# Sheet2.net
KiCad netlist of a schematic drawn in Altium Designer
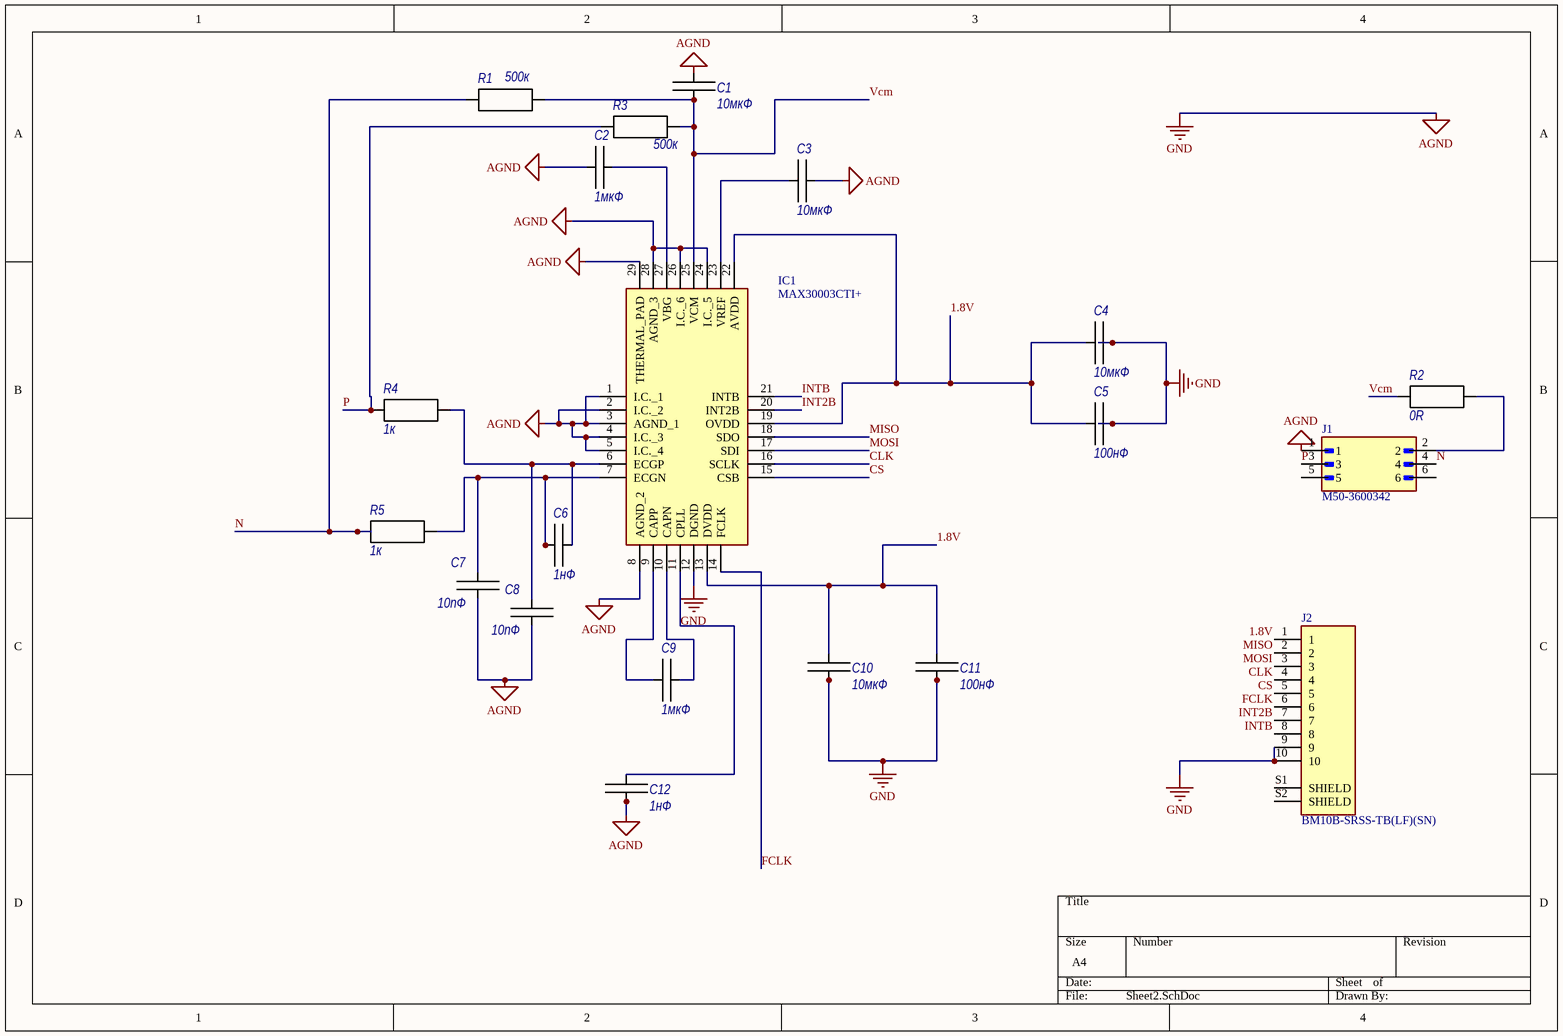
[diagram p0: Sheet2.SchDoc]

(export (version "E")
  (design (tool "Eeschema 10.0.6"))
  (components
    (comp (ref "C1")
      (value "10мкФ")
      (footprint "C0402C")
      (description "CC0402JRX7R9BB103, 0402 X5R 0,01 uF 50V")
      (fields (field (name "PART NUMBER") "CC0402JRX7R9BB103") (field (name "MANUFACTURER") "Yageo"))
      (libsource (lib "lib") (part "Cap"))
    )
    (comp (ref "C2")
      (value "1мкФ")
      (footprint "C0402C")
      (description "CC0402JRX7R9BB103, 0402 X5R 0,01 uF 50V")
      (fields (field (name "PART NUMBER") "CC0402JRX7R9BB103") (field (name "MANUFACTURER") "Yageo"))
      (libsource (lib "lib") (part "Cap"))
    )
    (comp (ref "C3")
      (value "10мкФ")
      (footprint "C0402C")
      (description "CC0402JRX7R9BB103, 0402 X5R 0,01 uF 50V")
      (fields (field (name "PART NUMBER") "CC0402JRX7R9BB103") (field (name "MANUFACTURER") "Yageo"))
      (libsource (lib "lib") (part "Cap"))
    )
    (comp (ref "C4")
      (value "10мкФ")
      (footprint "C0402C")
      (description "CC0402JRX7R9BB103, 0402 X5R 0,01 uF 50V")
      (fields (field (name "PART NUMBER") "CC0402JRX7R9BB103") (field (name "MANUFACTURER") "Yageo"))
      (libsource (lib "lib") (part "Cap"))
    )
    (comp (ref "C5")
      (value "100нФ")
      (footprint "C0402C")
      (description "CC0402JRX7R9BB103, 0402 X5R 0,01 uF 50V")
      (fields (field (name "PART NUMBER") "CC0402JRX7R9BB103") (field (name "MANUFACTURER") "Yageo"))
      (libsource (lib "lib") (part "Cap"))
    )
    (comp (ref "C6")
      (value "1нФ")
      (footprint "C0402C")
      (description "CC0402JRX7R9BB103, 0402 X5R 0,01 uF 50V")
      (fields (field (name "PART NUMBER") "CC0402JRX7R9BB103") (field (name "MANUFACTURER") "Yageo"))
      (libsource (lib "lib") (part "Cap"))
    )
    (comp (ref "C7")
      (value "10пФ")
      (footprint "C0402C")
      (description "CC0402JRX7R9BB103, 0402 X5R 0,01 uF 50V")
      (fields (field (name "PART NUMBER") "CC0402JRX7R9BB103") (field (name "MANUFACTURER") "Yageo"))
      (libsource (lib "lib") (part "Cap"))
    )
    (comp (ref "C8")
      (value "10пФ")
      (footprint "C0402C")
      (description "CC0402JRX7R9BB103, 0402 X5R 0,01 uF 50V")
      (fields (field (name "PART NUMBER") "CC0402JRX7R9BB103") (field (name "MANUFACTURER") "Yageo"))
      (libsource (lib "lib") (part "Cap"))
    )
    (comp (ref "C9")
      (value "1мкФ")
      (footprint "C0402C")
      (description "CC0402JRX7R9BB103, 0402 X5R 0,01 uF 50V")
      (fields (field (name "PART NUMBER") "CC0402JRX7R9BB103") (field (name "MANUFACTURER") "Yageo"))
      (libsource (lib "lib") (part "Cap"))
    )
    (comp (ref "C10")
      (value "10мкФ")
      (footprint "C0402C")
      (description "CC0402JRX7R9BB103, 0402 X5R 0,01 uF 50V")
      (fields (field (name "PART NUMBER") "CC0402JRX7R9BB103") (field (name "MANUFACTURER") "Yageo"))
      (libsource (lib "lib") (part "Cap"))
    )
    (comp (ref "C11")
      (value "100нФ")
      (footprint "C0402C")
      (description "CC0402JRX7R9BB103, 0402 X5R 0,01 uF 50V")
      (fields (field (name "PART NUMBER") "CC0402JRX7R9BB103") (field (name "MANUFACTURER") "Yageo"))
      (libsource (lib "lib") (part "Cap"))
    )
    (comp (ref "C12")
      (value "1нФ")
      (footprint "C0402C")
      (description "CC0402JRX7R9BB103, 0402 X5R 0,01 uF 50V")
      (fields (field (name "PART NUMBER") "CC0402JRX7R9BB103") (field (name "MANUFACTURER") "Yageo"))
      (libsource (lib "lib") (part "Cap"))
    )
    (comp (ref "IC1")
      (value "MAX30003CTI+")
      (footprint "QFN50P500X500X80-29N")
      (description "Integrated Circuit")
      (fields (field (name "MOUSER PART NUMBER") "700-MAX30003CTI+"))
      (libsource (lib "*") (part "MAX30003CTI+"))
    )
    (comp (ref "J1")
      (value "M50-3600342")
      (footprint "HARWIN_M50-3600342")
      (libsource (lib "M50-3600342") (part "M50-3600342"))
    )
    (comp (ref "J2")
      (value "BM10B-SRSS-TB(LF)(SN)")
      (footprint "JST_BM10B-SRSS-TB(LF)(SN)")
      (description "Connector Header Surface Mount 10 position 0.039 (1.00mm)")
      (fields (field (name "MF") "JST Sales"))
      (libsource (lib "BM10B-SRSS-TB_LF__SN_") (part "BM10B-SRSS-TB(LF)(SN)"))
    )
    (comp (ref "R1")
      (value "500к")
      (footprint "C0402R")
      (description "Р1-12М-0402-0,  SMD 0402")
      (fields (field (name "PART NUMBER") "Р1-12М-0402-0") (field (name "MANUFACTURER") "НПО ЭРКОН"))
      (libsource (lib "lib") (part "res"))
    )
    (comp (ref "R2")
      (value "0R")
      (footprint "C0402R")
      (description "Р1-12М-0402-0,  SMD 0402")
      (fields (field (name "PART NUMBER") "Р1-12М-0402-0") (field (name "MANUFACTURER") "НПО ЭРКОН"))
      (libsource (lib "lib") (part "res"))
    )
    (comp (ref "R3")
      (value "500к")
      (footprint "C0402R")
      (description "Р1-12М-0402-0,  SMD 0402")
      (fields (field (name "PART NUMBER") "Р1-12М-0402-0") (field (name "MANUFACTURER") "НПО ЭРКОН"))
      (libsource (lib "lib") (part "res"))
    )
    (comp (ref "R4")
      (value "1к")
      (footprint "C0402R")
      (description "Р1-12М-0402-0,  SMD 0402")
      (fields (field (name "PART NUMBER") "Р1-12М-0402-0") (field (name "MANUFACTURER") "НПО ЭРКОН"))
      (libsource (lib "lib") (part "res"))
    )
    (comp (ref "R5")
      (value "1к")
      (footprint "C0402R")
      (description "Р1-12М-0402-0,  SMD 0402")
      (fields (field (name "PART NUMBER") "Р1-12М-0402-0") (field (name "MANUFACTURER") "НПО ЭРКОН"))
      (libsource (lib "lib") (part "res"))
    )
  )
  (nets
    (net (code "1") (name "/1.8V") (class "Default")
      (node (ref "C10") (pin "1") (pinfunction "1_1") (pintype "passive"))
      (node (ref "C11") (pin "1") (pinfunction "1_1") (pintype "passive"))
      (node (ref "C4") (pin "1") (pinfunction "1_1") (pintype "passive"))
      (node (ref "C5") (pin "1") (pinfunction "1_1") (pintype "passive"))
      (node (ref "IC1") (pin "13") (pinfunction "DVDD_13") (pintype "passive"))
      (node (ref "IC1") (pin "19") (pinfunction "OVDD_19") (pintype "passive"))
      (node (ref "IC1") (pin "22") (pinfunction "AVDD_22") (pintype "passive"))
      (node (ref "J2") (pin "1") (pinfunction "1_1") (pintype "passive"))
    )
    (net (code "2") (name "/CLK") (class "Default")
      (node (ref "IC1") (pin "16") (pinfunction "SCLK_16") (pintype "passive"))
      (node (ref "J2") (pin "4") (pinfunction "4_4") (pintype "passive"))
    )
    (net (code "3") (name "/CS") (class "Default")
      (node (ref "IC1") (pin "15") (pinfunction "CSB_15") (pintype "passive"))
      (node (ref "J2") (pin "5") (pinfunction "5_5") (pintype "passive"))
    )
    (net (code "4") (name "/FCLK") (class "Default")
      (node (ref "IC1") (pin "14") (pinfunction "FCLK_14") (pintype "passive"))
      (node (ref "J2") (pin "6") (pinfunction "6_6") (pintype "passive"))
    )
    (net (code "5") (name "/INT2B") (class "Default")
      (node (ref "IC1") (pin "20") (pinfunction "INT2B_20") (pintype "passive"))
      (node (ref "J2") (pin "7") (pinfunction "7_7") (pintype "passive"))
    )
    (net (code "6") (name "/INTB") (class "Default")
      (node (ref "IC1") (pin "21") (pinfunction "INTB_21") (pintype "passive"))
      (node (ref "J2") (pin "8") (pinfunction "8_8") (pintype "passive"))
    )
    (net (code "7") (name "/MISO") (class "Default")
      (node (ref "IC1") (pin "18") (pinfunction "SDO_18") (pintype "passive"))
      (node (ref "J2") (pin "2") (pinfunction "2_2") (pintype "passive"))
    )
    (net (code "8") (name "/MOSI") (class "Default")
      (node (ref "IC1") (pin "17") (pinfunction "SDI_17") (pintype "passive"))
      (node (ref "J2") (pin "3") (pinfunction "3_3") (pintype "passive"))
    )
    (net (code "9") (name "/N") (class "Default")
      (node (ref "J1") (pin "4") (pinfunction "4_4") (pintype "passive"))
      (node (ref "R1") (pin "2") (pinfunction "2_2") (pintype "passive"))
      (node (ref "R5") (pin "2") (pinfunction "2_2") (pintype "passive"))
    )
    (net (code "10") (name "/P") (class "Default")
      (node (ref "J1") (pin "3") (pinfunction "3_3") (pintype "passive"))
      (node (ref "R3") (pin "2") (pinfunction "2_2") (pintype "passive"))
      (node (ref "R4") (pin "2") (pinfunction "2_2") (pintype "passive"))
    )
    (net (code "11") (name "/Vcm") (class "Default")
      (node (ref "C1") (pin "1") (pinfunction "1_1") (pintype "passive"))
      (node (ref "IC1") (pin "25") (pinfunction "VCM_25") (pintype "passive"))
      (node (ref "R1") (pin "1") (pinfunction "1_1") (pintype "passive"))
      (node (ref "R2") (pin "2") (pinfunction "2_2") (pintype "passive"))
      (node (ref "R3") (pin "1") (pinfunction "1_1") (pintype "passive"))
    )
    (net (code "12") (name "AGND") (class "Default")
      (node (ref "C1") (pin "2") (pinfunction "2_2") (pintype "passive"))
      (node (ref "C10") (pin "2") (pinfunction "2_2") (pintype "passive"))
      (node (ref "C11") (pin "2") (pinfunction "2_2") (pintype "passive"))
      (node (ref "C12") (pin "2") (pinfunction "2_2") (pintype "passive"))
      (node (ref "C2") (pin "2") (pinfunction "2_2") (pintype "passive"))
      (node (ref "C3") (pin "2") (pinfunction "2_2") (pintype "passive"))
      (node (ref "C4") (pin "2") (pinfunction "2_2") (pintype "passive"))
      (node (ref "C5") (pin "2") (pinfunction "2_2") (pintype "passive"))
      (node (ref "C7") (pin "1") (pinfunction "1_1") (pintype "passive"))
      (node (ref "C8") (pin "1") (pinfunction "1_1") (pintype "passive"))
      (node (ref "IC1") (pin "1") (pinfunction "I.C._1_1") (pintype "passive"))
      (node (ref "IC1") (pin "12") (pinfunction "DGND_12") (pintype "passive"))
      (node (ref "IC1") (pin "2") (pinfunction "I.C._2_2") (pintype "passive"))
      (node (ref "IC1") (pin "24") (pinfunction "I.C._5_24") (pintype "passive"))
      (node (ref "IC1") (pin "26") (pinfunction "I.C._6_26") (pintype "passive"))
      (node (ref "IC1") (pin "28") (pinfunction "AGND_3_28") (pintype "passive"))
      (node (ref "IC1") (pin "29") (pinfunction "THERMAL_PAD_29") (pintype "passive"))
      (node (ref "IC1") (pin "3") (pinfunction "AGND_1_3") (pintype "passive"))
      (node (ref "IC1") (pin "4") (pinfunction "I.C._3_4") (pintype "passive"))
      (node (ref "IC1") (pin "5") (pinfunction "I.C._4_5") (pintype "passive"))
      (node (ref "IC1") (pin "8") (pinfunction "AGND_2_8") (pintype "passive"))
      (node (ref "J1") (pin "1") (pinfunction "1_1") (pintype "passive"))
      (node (ref "J2") (pin "10") (pinfunction "10_10") (pintype "passive"))
      (node (ref "J2") (pin "9") (pinfunction "9_9") (pintype "passive"))
    )
    (net (code "13") (name "Net-(IC1-CAPN)") (class "Default")
      (node (ref "C9") (pin "1") (pinfunction "1_1") (pintype "passive"))
      (node (ref "IC1") (pin "10") (pinfunction "CAPN_10") (pintype "passive"))
    )
    (net (code "14") (name "Net-(IC1-CAPP)") (class "Default")
      (node (ref "C9") (pin "2") (pinfunction "2_2") (pintype "passive"))
      (node (ref "IC1") (pin "9") (pinfunction "CAPP_9") (pintype "passive"))
    )
    (net (code "15") (name "Net-(IC1-CPLL)") (class "Default")
      (node (ref "C12") (pin "1") (pinfunction "1_1") (pintype "passive"))
      (node (ref "IC1") (pin "11") (pinfunction "CPLL_11") (pintype "passive"))
    )
    (net (code "16") (name "Net-(IC1-ECGN)") (class "Default")
      (node (ref "C6") (pin "2") (pinfunction "2_2") (pintype "passive"))
      (node (ref "C7") (pin "2") (pinfunction "2_2") (pintype "passive"))
      (node (ref "IC1") (pin "7") (pinfunction "ECGN_7") (pintype "passive"))
      (node (ref "R5") (pin "1") (pinfunction "1_1") (pintype "passive"))
    )
    (net (code "17") (name "Net-(IC1-ECGP)") (class "Default")
      (node (ref "C6") (pin "1") (pinfunction "1_1") (pintype "passive"))
      (node (ref "C8") (pin "2") (pinfunction "2_2") (pintype "passive"))
      (node (ref "IC1") (pin "6") (pinfunction "ECGP_6") (pintype "passive"))
      (node (ref "R4") (pin "1") (pinfunction "1_1") (pintype "passive"))
    )
    (net (code "18") (name "Net-(IC1-VBG)") (class "Default")
      (node (ref "C2") (pin "1") (pinfunction "1_1") (pintype "passive"))
      (node (ref "IC1") (pin "27") (pinfunction "VBG_27") (pintype "passive"))
    )
    (net (code "19") (name "Net-(IC1-VREF)") (class "Default")
      (node (ref "C3") (pin "1") (pinfunction "1_1") (pintype "passive"))
      (node (ref "IC1") (pin "23") (pinfunction "VREF_23") (pintype "passive"))
    )
    (net (code "20") (name "Net-(J1-Pad2)") (class "Default")
      (node (ref "J1") (pin "2") (pinfunction "2_2") (pintype "passive"))
      (node (ref "R2") (pin "1") (pinfunction "1_1") (pintype "passive"))
    )
    (net (code "21") (name "unconnected-(J1-Pad5)") (class "Default")
      (node (ref "J1") (pin "5") (pinfunction "5_5") (pintype "passive"))
    )
    (net (code "22") (name "unconnected-(J1-Pad6)") (class "Default")
      (node (ref "J1") (pin "6") (pinfunction "6_6") (pintype "passive"))
    )
    (net (code "23") (name "unconnected-(J2-SHIELD-PadS1)") (class "Default")
      (node (ref "J2") (pin "S1") (pinfunction "SHIELD_S1") (pintype "passive"))
    )
    (net (code "24") (name "unconnected-(J2-SHIELD-PadS2)") (class "Default")
      (node (ref "J2") (pin "S2") (pinfunction "SHIELD_S2") (pintype "passive"))
    )
  )
)
